# DebugLEDs.net
KiCad netlist of a schematic drawn in Altium Designer
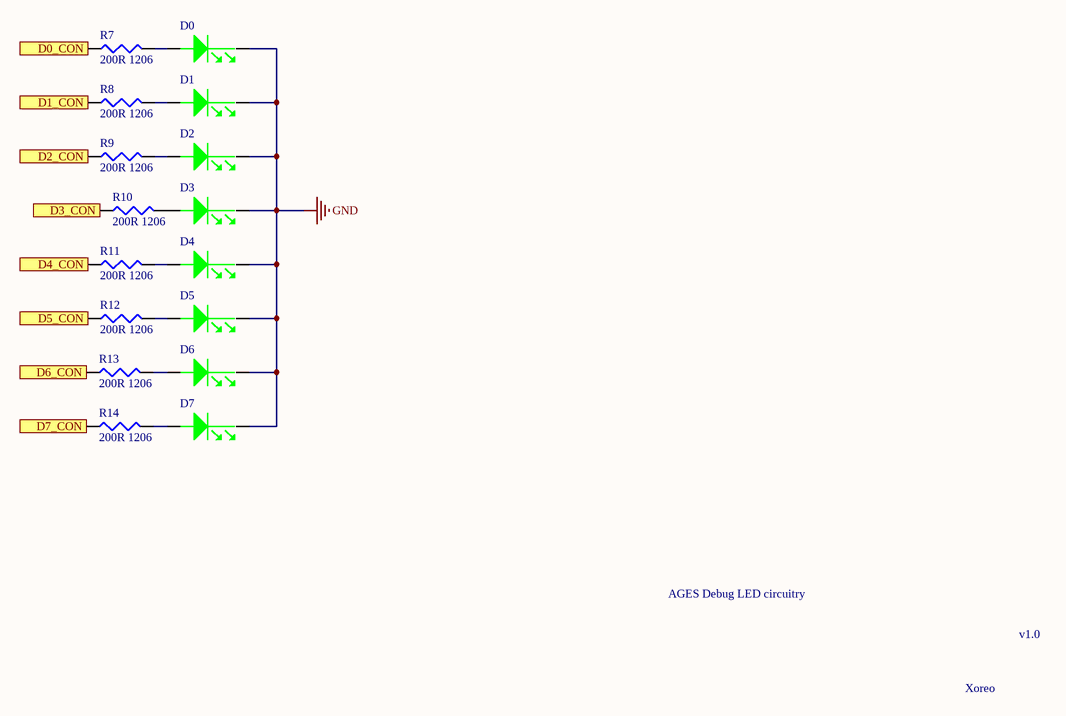
[diagram p0: DebugLEDs.SchDoc]

(export (version "E")
  (design (tool "Eeschema 10.0.6"))
  (components
    (comp (ref "D0")
      (value "LEDG")
      (footprint "LEDC3216X120N")
      (description "LED Uni-Color SB. Green 565nm 2-Pin Chip LED T/R")
      (fields
        (field (name "MANUFACTURER") "Kingbright")
        (field (name "MANUFACTURER PART NUMBER") "KPT-3216SGC")
      )
      (libsource (lib "Mobo") (part "LED"))
    )
    (comp (ref "D1")
      (value "LEDG")
      (footprint "LEDC3216X120N")
      (description "LED Uni-Color SB. Green 565nm 2-Pin Chip LED T/R")
      (fields
        (field (name "MANUFACTURER") "Kingbright")
        (field (name "MANUFACTURER PART NUMBER") "KPT-3216SGC")
      )
      (libsource (lib "Mobo") (part "LED"))
    )
    (comp (ref "D2")
      (value "LEDG")
      (footprint "LEDC3216X120N")
      (description "LED Uni-Color SB. Green 565nm 2-Pin Chip LED T/R")
      (fields
        (field (name "MANUFACTURER") "Kingbright")
        (field (name "MANUFACTURER PART NUMBER") "KPT-3216SGC")
      )
      (libsource (lib "Mobo") (part "LED"))
    )
    (comp (ref "D3")
      (value "LEDG")
      (footprint "LEDC3216X120N")
      (description "LED Uni-Color SB. Green 565nm 2-Pin Chip LED T/R")
      (fields
        (field (name "MANUFACTURER") "Kingbright")
        (field (name "MANUFACTURER PART NUMBER") "KPT-3216SGC")
      )
      (libsource (lib "Mobo") (part "LED"))
    )
    (comp (ref "D4")
      (value "LEDG")
      (footprint "LEDC3216X120N")
      (description "LED Uni-Color SB. Green 565nm 2-Pin Chip LED T/R")
      (fields
        (field (name "MANUFACTURER") "Kingbright")
        (field (name "MANUFACTURER PART NUMBER") "KPT-3216SGC")
      )
      (libsource (lib "Mobo") (part "LED"))
    )
    (comp (ref "D5")
      (value "LEDG")
      (footprint "LEDC3216X120N")
      (description "LED Uni-Color SB. Green 565nm 2-Pin Chip LED T/R")
      (fields
        (field (name "MANUFACTURER") "Kingbright")
        (field (name "MANUFACTURER PART NUMBER") "KPT-3216SGC")
      )
      (libsource (lib "Mobo") (part "LED"))
    )
    (comp (ref "D6")
      (value "LEDG")
      (footprint "LEDC3216X120N")
      (description "LED Uni-Color SB. Green 565nm 2-Pin Chip LED T/R")
      (fields
        (field (name "MANUFACTURER") "Kingbright")
        (field (name "MANUFACTURER PART NUMBER") "KPT-3216SGC")
      )
      (libsource (lib "Mobo") (part "LED"))
    )
    (comp (ref "D7")
      (value "LEDG")
      (footprint "LEDC3216X120N")
      (description "LED Uni-Color SB. Green 565nm 2-Pin Chip LED T/R")
      (fields
        (field (name "MANUFACTURER") "Kingbright")
        (field (name "MANUFACTURER PART NUMBER") "KPT-3216SGC")
      )
      (libsource (lib "Mobo") (part "LED"))
    )
    (comp (ref "R7")
      (value "200R 1206")
      (footprint "Resistor 1206")
      (description "Surface Mount Thick Film Resistor, AEC-Q200 ERJ Series, 200 ohm, 250 mW, - 1%, 200 V")
      (fields
        (field (name "MANUFACTURER") "Panasonic")
        (field (name "MANUFACTURER PART NUMBER") "ERJ-U08F2000V")
      )
      (libsource (lib "Mobo") (part "Resistor{colon} 200R"))
    )
    (comp (ref "R8")
      (value "200R 1206")
      (footprint "Resistor 1206")
      (description "Surface Mount Thick Film Resistor, AEC-Q200 ERJ Series, 200 ohm, 250 mW, - 1%, 200 V")
      (fields
        (field (name "MANUFACTURER") "Panasonic")
        (field (name "MANUFACTURER PART NUMBER") "ERJ-U08F2000V")
      )
      (libsource (lib "Mobo") (part "Resistor{colon} 200R"))
    )
    (comp (ref "R9")
      (value "200R 1206")
      (footprint "Resistor 1206")
      (description "Surface Mount Thick Film Resistor, AEC-Q200 ERJ Series, 200 ohm, 250 mW, - 1%, 200 V")
      (fields
        (field (name "MANUFACTURER") "Panasonic")
        (field (name "MANUFACTURER PART NUMBER") "ERJ-U08F2000V")
      )
      (libsource (lib "Mobo") (part "Resistor{colon} 200R"))
    )
    (comp (ref "R10")
      (value "200R 1206")
      (footprint "Resistor 1206")
      (description "Surface Mount Thick Film Resistor, AEC-Q200 ERJ Series, 200 ohm, 250 mW, - 1%, 200 V")
      (fields
        (field (name "MANUFACTURER") "Panasonic")
        (field (name "MANUFACTURER PART NUMBER") "ERJ-U08F2000V")
      )
      (libsource (lib "Mobo") (part "Resistor{colon} 200R"))
    )
    (comp (ref "R11")
      (value "200R 1206")
      (footprint "Resistor 1206")
      (description "Surface Mount Thick Film Resistor, AEC-Q200 ERJ Series, 200 ohm, 250 mW, - 1%, 200 V")
      (fields
        (field (name "MANUFACTURER") "Panasonic")
        (field (name "MANUFACTURER PART NUMBER") "ERJ-U08F2000V")
      )
      (libsource (lib "Mobo") (part "Resistor{colon} 200R"))
    )
    (comp (ref "R12")
      (value "200R 1206")
      (footprint "Resistor 1206")
      (description "Surface Mount Thick Film Resistor, AEC-Q200 ERJ Series, 200 ohm, 250 mW, - 1%, 200 V")
      (fields
        (field (name "MANUFACTURER") "Panasonic")
        (field (name "MANUFACTURER PART NUMBER") "ERJ-U08F2000V")
      )
      (libsource (lib "Mobo") (part "Resistor{colon} 200R"))
    )
    (comp (ref "R13")
      (value "200R 1206")
      (footprint "Resistor 1206")
      (description "Surface Mount Thick Film Resistor, AEC-Q200 ERJ Series, 200 ohm, 250 mW, - 1%, 200 V")
      (fields
        (field (name "MANUFACTURER") "Panasonic")
        (field (name "MANUFACTURER PART NUMBER") "ERJ-U08F2000V")
      )
      (libsource (lib "Mobo") (part "Resistor{colon} 200R"))
    )
    (comp (ref "R14")
      (value "200R 1206")
      (footprint "Resistor 1206")
      (description "Surface Mount Thick Film Resistor, AEC-Q200 ERJ Series, 200 ohm, 250 mW, - 1%, 200 V")
      (fields
        (field (name "MANUFACTURER") "Panasonic")
        (field (name "MANUFACTURER PART NUMBER") "ERJ-U08F2000V")
      )
      (libsource (lib "Mobo") (part "Resistor{colon} 200R"))
    )
  )
  (nets
    (net (code "1") (name "/D0_CON") (class "Default")
      (node (ref "R7") (pin "1") (pinfunction "1_1") (pintype "passive"))
    )
    (net (code "2") (name "/D1_CON") (class "Default")
      (node (ref "R8") (pin "1") (pinfunction "1_1") (pintype "passive"))
    )
    (net (code "3") (name "/D2_CON") (class "Default")
      (node (ref "R9") (pin "1") (pinfunction "1_1") (pintype "passive"))
    )
    (net (code "4") (name "/D3_CON") (class "Default")
      (node (ref "R10") (pin "1") (pinfunction "1_1") (pintype "passive"))
    )
    (net (code "5") (name "/D4_CON") (class "Default")
      (node (ref "R11") (pin "1") (pinfunction "1_1") (pintype "passive"))
    )
    (net (code "6") (name "/D5_CON") (class "Default")
      (node (ref "R12") (pin "1") (pinfunction "1_1") (pintype "passive"))
    )
    (net (code "7") (name "/D6_CON") (class "Default")
      (node (ref "R13") (pin "1") (pinfunction "1_1") (pintype "passive"))
    )
    (net (code "8") (name "/D7_CON") (class "Default")
      (node (ref "R14") (pin "1") (pinfunction "1_1") (pintype "passive"))
    )
    (net (code "9") (name "GND") (class "Default")
      (node (ref "D0") (pin "NEG") (pinfunction "+_NEG") (pintype "passive"))
      (node (ref "D1") (pin "NEG") (pinfunction "+_NEG") (pintype "passive"))
      (node (ref "D2") (pin "NEG") (pinfunction "+_NEG") (pintype "passive"))
      (node (ref "D3") (pin "NEG") (pinfunction "+_NEG") (pintype "passive"))
      (node (ref "D4") (pin "NEG") (pinfunction "+_NEG") (pintype "passive"))
      (node (ref "D5") (pin "NEG") (pinfunction "+_NEG") (pintype "passive"))
      (node (ref "D6") (pin "NEG") (pinfunction "+_NEG") (pintype "passive"))
      (node (ref "D7") (pin "NEG") (pinfunction "+_NEG") (pintype "passive"))
    )
    (net (code "10") (name "Net-(D0-2)") (class "Default")
      (node (ref "D0") (pin "POS") (pinfunction "2_POS") (pintype "passive"))
      (node (ref "R7") (pin "2") (pinfunction "2_2") (pintype "passive"))
    )
    (net (code "11") (name "Net-(D1-2)") (class "Default")
      (node (ref "D1") (pin "POS") (pinfunction "2_POS") (pintype "passive"))
      (node (ref "R8") (pin "2") (pinfunction "2_2") (pintype "passive"))
    )
    (net (code "12") (name "Net-(D2-2)") (class "Default")
      (node (ref "D2") (pin "POS") (pinfunction "2_POS") (pintype "passive"))
      (node (ref "R9") (pin "2") (pinfunction "2_2") (pintype "passive"))
    )
    (net (code "13") (name "Net-(D3-2)") (class "Default")
      (node (ref "D3") (pin "POS") (pinfunction "2_POS") (pintype "passive"))
      (node (ref "R10") (pin "2") (pinfunction "2_2") (pintype "passive"))
    )
    (net (code "14") (name "Net-(D4-2)") (class "Default")
      (node (ref "D4") (pin "POS") (pinfunction "2_POS") (pintype "passive"))
      (node (ref "R11") (pin "2") (pinfunction "2_2") (pintype "passive"))
    )
    (net (code "15") (name "Net-(D5-2)") (class "Default")
      (node (ref "D5") (pin "POS") (pinfunction "2_POS") (pintype "passive"))
      (node (ref "R12") (pin "2") (pinfunction "2_2") (pintype "passive"))
    )
    (net (code "16") (name "Net-(D6-2)") (class "Default")
      (node (ref "D6") (pin "POS") (pinfunction "2_POS") (pintype "passive"))
      (node (ref "R13") (pin "2") (pinfunction "2_2") (pintype "passive"))
    )
    (net (code "17") (name "Net-(D7-2)") (class "Default")
      (node (ref "D7") (pin "POS") (pinfunction "2_POS") (pintype "passive"))
      (node (ref "R14") (pin "2") (pinfunction "2_2") (pintype "passive"))
    )
  )
)
